# brushed_UAS_Design_2_routed.net
KiCad netlist of a schematic drawn in EAGLE
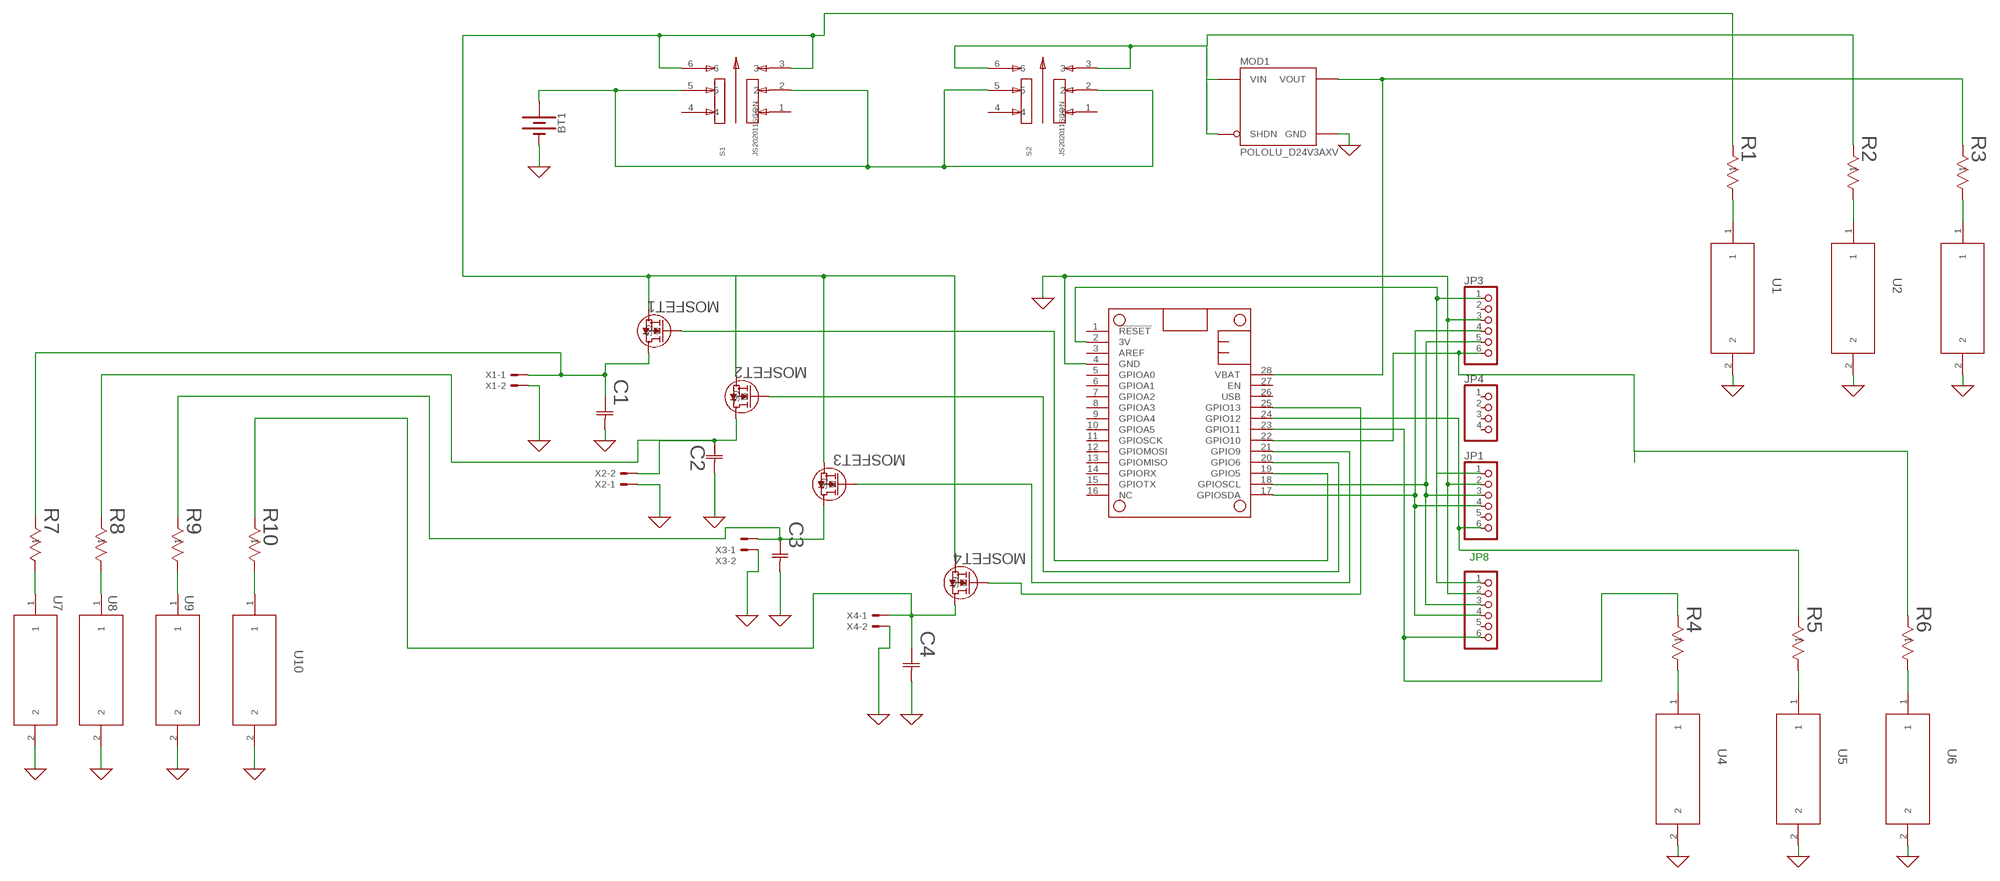
[diagram p0: schematic, sheet 1, part 1 of 2]
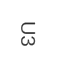
[diagram p1: schematic, sheet 1, part 2 of 2]

(export (version "E")
  (design (tool "Eeschema 10.0.6"))
  (components
    (comp (ref "BT1")
      (value "BATTERY-18650")
      (footprint "eagle-import:BATTERY_18650-HOLDER")
      (libsource (lib "eagle-import") (part "BATTERY-18650"))
    )
    (comp (ref "C1")
      (value "ECH-U1H102JX5CAP_J1_PAN-M")
      (footprint "eagle-import:CAP_J1_PAN-M")
      (fields (field (name "MANUFACTURER_PART_NUMBER") "ECH-U1H102JX5"))
      (libsource (lib "eagle-import") (part "ECH-U1H102JX5CAP_J1_PAN-M"))
    )
    (comp (ref "C2")
      (value "ECH-U1H102JX5CAP_J1_PAN-M")
      (footprint "eagle-import:CAP_J1_PAN-M")
      (fields (field (name "MANUFACTURER_PART_NUMBER") "ECH-U1H102JX5"))
      (libsource (lib "eagle-import") (part "ECH-U1H102JX5CAP_J1_PAN-M"))
    )
    (comp (ref "C3")
      (value "ECH-U1H102JX5CAP_J1_PAN-M")
      (footprint "eagle-import:CAP_J1_PAN-M")
      (fields (field (name "MANUFACTURER_PART_NUMBER") "ECH-U1H102JX5"))
      (libsource (lib "eagle-import") (part "ECH-U1H102JX5CAP_J1_PAN-M"))
    )
    (comp (ref "C4")
      (value "ECH-U1H102JX5CAP_J1_PAN-M")
      (footprint "eagle-import:CAP_J1_PAN-M")
      (fields (field (name "MANUFACTURER_PART_NUMBER") "ECH-U1H102JX5"))
      (libsource (lib "eagle-import") (part "ECH-U1H102JX5CAP_J1_PAN-M"))
    )
    (comp (ref "JP1")
      (value "HEADER-1X670MIL")
      (footprint "eagle-import:1X06_ROUND_70")
      (libsource (lib "eagle-import") (part "HEADER-1X670MIL"))
    )
    (comp (ref "JP3")
      (value "HEADER-1X676MIL")
      (footprint "eagle-import:1X06_ROUND_76")
      (libsource (lib "eagle-import") (part "HEADER-1X676MIL"))
    )
    (comp (ref "JP4")
      (value "HEADER-1X476MIL")
      (footprint "eagle-import:1X04_ROUND_76")
      (libsource (lib "eagle-import") (part "HEADER-1X476MIL"))
    )
    (comp (ref "JP8")
      (value "HEADER-1X670MIL")
      (footprint "eagle-import:1X06_ROUND_70")
      (libsource (lib "eagle-import") (part "HEADER-1X670MIL"))
    )
    (comp (ref "MOD1")
      (value "POLOLU_D24V3AXV")
      (footprint "eagle-import:POLOLU_D24VXAYV_HC")
      (libsource (lib "eagle-import") (part "POLOLU_D24V3AVX"))
    )
    (comp (ref "MOSFET1")
      (value "SI2342DS-T1-GE3SOT-23_TO-236_VIS-M")
      (footprint "eagle-import:SOT-23_TO-236_VIS-M")
      (fields
        (field (name "MANUFACTURER_PART_NUMBER") "SI2342DS-T1-GE3")
        (field (name "COPYRIGHT") "Copyright (C) 2018 Accelerated Designs. All rights reserved")
      )
      (libsource (lib "eagle-import") (part "SI2342DS-T1-GE3SOT-23_TO-236_VIS-M"))
    )
    (comp (ref "MOSFET2")
      (value "SI2342DS-T1-GE3SOT-23_TO-236_VIS-M")
      (footprint "eagle-import:SOT-23_TO-236_VIS-M")
      (fields
        (field (name "MANUFACTURER_PART_NUMBER") "SI2342DS-T1-GE3")
        (field (name "COPYRIGHT") "Copyright (C) 2018 Accelerated Designs. All rights reserved")
      )
      (libsource (lib "eagle-import") (part "SI2342DS-T1-GE3SOT-23_TO-236_VIS-M"))
    )
    (comp (ref "MOSFET3")
      (value "SI2342DS-T1-GE3SOT-23_TO-236_VIS-M")
      (footprint "eagle-import:SOT-23_TO-236_VIS-M")
      (fields
        (field (name "MANUFACTURER_PART_NUMBER") "SI2342DS-T1-GE3")
        (field (name "COPYRIGHT") "Copyright (C) 2018 Accelerated Designs. All rights reserved")
      )
      (libsource (lib "eagle-import") (part "SI2342DS-T1-GE3SOT-23_TO-236_VIS-M"))
    )
    (comp (ref "MOSFET4")
      (value "SI2342DS-T1-GE3SOT-23_TO-236_VIS-M")
      (footprint "eagle-import:SOT-23_TO-236_VIS-M")
      (fields
        (field (name "MANUFACTURER_PART_NUMBER") "SI2342DS-T1-GE3")
        (field (name "COPYRIGHT") "Copyright (C) 2018 Accelerated Designs. All rights reserved")
      )
      (libsource (lib "eagle-import") (part "SI2342DS-T1-GE3SOT-23_TO-236_VIS-M"))
    )
    (comp (ref "MS1")
      (value "FEATHERWING_NODIM")
      (footprint "eagle-import:FEATHERWING_DIM")
      (libsource (lib "eagle-import") (part "FEATHERWING_NODIM"))
    )
    (comp (ref "R1")
      (value "CR0805-FX-1000ELFBO_CR0805-M")
      (footprint "eagle-import:BO_CR0805-M")
      (fields (field (name "MANUFACTURER_PART_NUMBER") "CR0805-FX-1000ELF"))
      (libsource (lib "eagle-import") (part "CR0805-FX-1000ELFBO_CR0805-M"))
    )
    (comp (ref "R2")
      (value "CR0805-FX-1000ELFBO_CR0805-M")
      (footprint "eagle-import:BO_CR0805-M")
      (fields (field (name "MANUFACTURER_PART_NUMBER") "CR0805-FX-1000ELF"))
      (libsource (lib "eagle-import") (part "CR0805-FX-1000ELFBO_CR0805-M"))
    )
    (comp (ref "R3")
      (value "CR0805-FX-1000ELFBO_CR0805-M")
      (footprint "eagle-import:BO_CR0805-M")
      (fields (field (name "MANUFACTURER_PART_NUMBER") "CR0805-FX-1000ELF"))
      (libsource (lib "eagle-import") (part "CR0805-FX-1000ELFBO_CR0805-M"))
    )
    (comp (ref "R4")
      (value "CR0805-FX-1000ELFBO_CR0805-M")
      (footprint "eagle-import:BO_CR0805-M")
      (fields (field (name "MANUFACTURER_PART_NUMBER") "CR0805-FX-1000ELF"))
      (libsource (lib "eagle-import") (part "CR0805-FX-1000ELFBO_CR0805-M"))
    )
    (comp (ref "R5")
      (value "CR0805-FX-1000ELFBO_CR0805-M")
      (footprint "eagle-import:BO_CR0805-M")
      (fields (field (name "MANUFACTURER_PART_NUMBER") "CR0805-FX-1000ELF"))
      (libsource (lib "eagle-import") (part "CR0805-FX-1000ELFBO_CR0805-M"))
    )
    (comp (ref "R6")
      (value "CR0805-FX-1000ELFBO_CR0805-M")
      (footprint "eagle-import:BO_CR0805-M")
      (fields (field (name "MANUFACTURER_PART_NUMBER") "CR0805-FX-1000ELF"))
      (libsource (lib "eagle-import") (part "CR0805-FX-1000ELFBO_CR0805-M"))
    )
    (comp (ref "R7")
      (value "CR0805-FX-1000ELFBO_CR0805-M")
      (footprint "eagle-import:BO_CR0805-M")
      (fields (field (name "MANUFACTURER_PART_NUMBER") "CR0805-FX-1000ELF"))
      (libsource (lib "eagle-import") (part "CR0805-FX-1000ELFBO_CR0805-M"))
    )
    (comp (ref "R8")
      (value "CR0805-FX-1000ELFBO_CR0805-M")
      (footprint "eagle-import:BO_CR0805-M")
      (fields (field (name "MANUFACTURER_PART_NUMBER") "CR0805-FX-1000ELF"))
      (libsource (lib "eagle-import") (part "CR0805-FX-1000ELFBO_CR0805-M"))
    )
    (comp (ref "R9")
      (value "CR0805-FX-1000ELFBO_CR0805-M")
      (footprint "eagle-import:BO_CR0805-M")
      (fields (field (name "MANUFACTURER_PART_NUMBER") "CR0805-FX-1000ELF"))
      (libsource (lib "eagle-import") (part "CR0805-FX-1000ELFBO_CR0805-M"))
    )
    (comp (ref "R10")
      (value "CR0805-FX-1000ELFBO_CR0805-M")
      (footprint "eagle-import:BO_CR0805-M")
      (fields (field (name "MANUFACTURER_PART_NUMBER") "CR0805-FX-1000ELF"))
      (libsource (lib "eagle-import") (part "CR0805-FX-1000ELFBO_CR0805-M"))
    )
    (comp (ref "S1")
      (value "JS202011SCQN")
      (footprint "eagle-import:SW_JS202011SCQN")
      (fields (field (name "DIGI-KEY_PART_NUMBER") "401-2002-1-ND") (field (name "MF") "C&K"))
      (libsource (lib "eagle-import") (part "JS202011SCQN"))
    )
    (comp (ref "S2")
      (value "JS202011SCQN")
      (footprint "eagle-import:SW_JS202011SCQN")
      (fields (field (name "DIGI-KEY_PART_NUMBER") "401-2002-1-ND") (field (name "MF") "C&K"))
      (libsource (lib "eagle-import") (part "JS202011SCQN"))
    )
    (comp (ref "U1")
      (value "L196L-QBCL196L-QBC_AOP-M")
      (footprint "eagle-import:L196L-QBC_AOP-M")
      (fields
        (field (name "MANUFACTURER_PART_NUMBER") "L196L-QBC")
        (field (name "COPYRIGHT") "Copyright (C) 2018 Accelerated Designs. All rights reserved")
      )
      (libsource (lib "eagle-import") (part "L196L-QBCL196L-QBC_AOP-M"))
    )
    (comp (ref "U2")
      (value "L196L-QBCL196L-QBC_AOP-M")
      (footprint "eagle-import:L196L-QBC_AOP-M")
      (fields
        (field (name "MANUFACTURER_PART_NUMBER") "L196L-QBC")
        (field (name "COPYRIGHT") "Copyright (C) 2018 Accelerated Designs. All rights reserved")
      )
      (libsource (lib "eagle-import") (part "L196L-QBCL196L-QBC_AOP-M"))
    )
    (comp (ref "U3")
      (value "L196L-QBCL196L-QBC_AOP-M")
      (footprint "eagle-import:L196L-QBC_AOP-M")
      (fields
        (field (name "MANUFACTURER_PART_NUMBER") "L196L-QBC")
        (field (name "COPYRIGHT") "Copyright (C) 2018 Accelerated Designs. All rights reserved")
      )
      (libsource (lib "eagle-import") (part "L196L-QBCL196L-QBC_AOP-M"))
    )
    (comp (ref "U4")
      (value "L196L-QBCL196L-QBC_AOP-M")
      (footprint "eagle-import:L196L-QBC_AOP-M")
      (fields
        (field (name "MANUFACTURER_PART_NUMBER") "L196L-QBC")
        (field (name "COPYRIGHT") "Copyright (C) 2018 Accelerated Designs. All rights reserved")
      )
      (libsource (lib "eagle-import") (part "L196L-QBCL196L-QBC_AOP-M"))
    )
    (comp (ref "U5")
      (value "L196L-QBCL196L-QBC_AOP-M")
      (footprint "eagle-import:L196L-QBC_AOP-M")
      (fields
        (field (name "MANUFACTURER_PART_NUMBER") "L196L-QBC")
        (field (name "COPYRIGHT") "Copyright (C) 2018 Accelerated Designs. All rights reserved")
      )
      (libsource (lib "eagle-import") (part "L196L-QBCL196L-QBC_AOP-M"))
    )
    (comp (ref "U6")
      (value "L196L-QBCL196L-QBC_AOP-M")
      (footprint "eagle-import:L196L-QBC_AOP-M")
      (fields
        (field (name "MANUFACTURER_PART_NUMBER") "L196L-QBC")
        (field (name "COPYRIGHT") "Copyright (C) 2018 Accelerated Designs. All rights reserved")
      )
      (libsource (lib "eagle-import") (part "L196L-QBCL196L-QBC_AOP-M"))
    )
    (comp (ref "U7")
      (value "L196L-QBCL196L-QBC_AOP-M")
      (footprint "eagle-import:L196L-QBC_AOP-M")
      (fields
        (field (name "MANUFACTURER_PART_NUMBER") "L196L-QBC")
        (field (name "COPYRIGHT") "Copyright (C) 2018 Accelerated Designs. All rights reserved")
      )
      (libsource (lib "eagle-import") (part "L196L-QBCL196L-QBC_AOP-M"))
    )
    (comp (ref "U8")
      (value "L196L-QBCL196L-QBC_AOP-M")
      (footprint "eagle-import:L196L-QBC_AOP-M")
      (fields
        (field (name "MANUFACTURER_PART_NUMBER") "L196L-QBC")
        (field (name "COPYRIGHT") "Copyright (C) 2018 Accelerated Designs. All rights reserved")
      )
      (libsource (lib "eagle-import") (part "L196L-QBCL196L-QBC_AOP-M"))
    )
    (comp (ref "U9")
      (value "L196L-QBCL196L-QBC_AOP-M")
      (footprint "eagle-import:L196L-QBC_AOP-M")
      (fields
        (field (name "MANUFACTURER_PART_NUMBER") "L196L-QBC")
        (field (name "COPYRIGHT") "Copyright (C) 2018 Accelerated Designs. All rights reserved")
      )
      (libsource (lib "eagle-import") (part "L196L-QBCL196L-QBC_AOP-M"))
    )
    (comp (ref "U10")
      (value "L196L-QBCL196L-QBC_AOP-M")
      (footprint "eagle-import:L196L-QBC_AOP-M")
      (fields
        (field (name "MANUFACTURER_PART_NUMBER") "L196L-QBC")
        (field (name "COPYRIGHT") "Copyright (C) 2018 Accelerated Designs. All rights reserved")
      )
      (libsource (lib "eagle-import") (part "L196L-QBCL196L-QBC_AOP-M"))
    )
    (comp (ref "X1")
      (value "22-23-2021")
      (footprint "eagle-import:22-23-2021")
      (fields (field (name "MF") "MOLEX"))
      (libsource (lib "eagle-import") (part "22-23-2021"))
    )
    (comp (ref "X2")
      (value "22-23-2021")
      (footprint "eagle-import:22-23-2021")
      (fields (field (name "MF") "MOLEX"))
      (libsource (lib "eagle-import") (part "22-23-2021"))
    )
    (comp (ref "X3")
      (value "22-23-2021")
      (footprint "eagle-import:22-23-2021")
      (fields (field (name "MF") "MOLEX"))
      (libsource (lib "eagle-import") (part "22-23-2021"))
    )
    (comp (ref "X4")
      (value "22-23-2021")
      (footprint "eagle-import:22-23-2021")
      (fields (field (name "MF") "MOLEX"))
      (libsource (lib "eagle-import") (part "22-23-2021"))
    )
  )
  (nets
    (net (code "1") (name "/USB") (class "Default")
      (node (ref "MS1") (pin "26") (pinfunction "USB_26") (pintype "power_in"))
    )
    (net (code "2") (name "GND") (class "Default")
      (node (ref "BT1") (pin "GND@1") (pinfunction "-_GND@1") (pintype "power_in"))
      (node (ref "C1") (pin "2") (pinfunction "2_2") (pintype "passive"))
      (node (ref "C2") (pin "2") (pinfunction "2_2") (pintype "passive"))
      (node (ref "C3") (pin "2") (pinfunction "2_2") (pintype "passive"))
      (node (ref "C4") (pin "2") (pinfunction "2_2") (pintype "passive"))
      (node (ref "JP1") (pin "2") (pinfunction "2_2") (pintype "passive"))
      (node (ref "JP3") (pin "3") (pinfunction "3_3") (pintype "passive"))
      (node (ref "JP8") (pin "2") (pinfunction "2_2") (pintype "passive"))
      (node (ref "MOD1") (pin "G") (pinfunction "GND_G") (pintype "power_in"))
      (node (ref "MS1") (pin "4") (pinfunction "GND_4") (pintype "power_in"))
      (node (ref "U1") (pin "2") (pinfunction "2_2") (pintype "passive"))
      (node (ref "U10") (pin "2") (pinfunction "2_2") (pintype "passive"))
      (node (ref "U2") (pin "2") (pinfunction "2_2") (pintype "passive"))
      (node (ref "U3") (pin "2") (pinfunction "2_2") (pintype "passive"))
      (node (ref "U4") (pin "2") (pinfunction "2_2") (pintype "passive"))
      (node (ref "U5") (pin "2") (pinfunction "2_2") (pintype "passive"))
      (node (ref "U6") (pin "2") (pinfunction "2_2") (pintype "passive"))
      (node (ref "U7") (pin "2") (pinfunction "2_2") (pintype "passive"))
      (node (ref "U8") (pin "2") (pinfunction "2_2") (pintype "passive"))
      (node (ref "U9") (pin "2") (pinfunction "2_2") (pintype "passive"))
      (node (ref "X1") (pin "2") (pinfunction "S_2") (pintype "passive"))
      (node (ref "X2") (pin "1") (pinfunction "S_1") (pintype "passive"))
      (node (ref "X3") (pin "2") (pinfunction "S_2") (pintype "passive"))
      (node (ref "X4") (pin "2") (pinfunction "S_2") (pintype "passive"))
    )
    (net (code "3") (name "Net-(BT1-+)") (class "Default")
      (node (ref "BT1") (pin "PWR@1") (pinfunction "+_PWR@1") (pintype "power_in"))
      (node (ref "S1") (pin "2") (pinfunction "2_2") (pintype "passive"))
      (node (ref "S1") (pin "5") (pinfunction "5_5") (pintype "passive"))
      (node (ref "S2") (pin "2") (pinfunction "2_2") (pintype "passive"))
      (node (ref "S2") (pin "5") (pinfunction "5_5") (pintype "passive"))
    )
    (net (code "4") (name "Net-(MOD1-SHDN)") (class "Default")
      (node (ref "MOD1") (pin "I") (pinfunction "VIN_I") (pintype "power_in"))
      (node (ref "MOD1") (pin "S") (pinfunction "SHDN_S") (pintype "input"))
      (node (ref "R2") (pin "1") (pinfunction "1_1") (pintype "passive"))
      (node (ref "S2") (pin "3") (pinfunction "3_3") (pintype "passive"))
      (node (ref "S2") (pin "6") (pinfunction "6_6") (pintype "passive"))
    )
    (net (code "5") (name "Net-(MOD1-VOUT)") (class "Default")
      (node (ref "MOD1") (pin "O") (pinfunction "VOUT_O") (pintype "output"))
      (node (ref "MS1") (pin "28") (pinfunction "VBAT_28") (pintype "power_in"))
      (node (ref "R3") (pin "1") (pinfunction "1_1") (pintype "passive"))
    )
    (net (code "6") (name "Net-(MOSFET1-D)") (class "Default")
      (node (ref "C1") (pin "1") (pinfunction "1_1") (pintype "passive"))
      (node (ref "MOSFET1") (pin "3") (pinfunction "D_3") (pintype "passive"))
      (node (ref "R7") (pin "1") (pinfunction "1_1") (pintype "passive"))
      (node (ref "X1") (pin "1") (pinfunction "S_1") (pintype "passive"))
    )
    (net (code "7") (name "Net-(MOSFET1-G)") (class "Default")
      (node (ref "MOSFET1") (pin "1") (pinfunction "G_1") (pintype "passive"))
      (node (ref "MS1") (pin "19") (pinfunction "GPIO5_19") (pintype "bidirectional"))
    )
    (net (code "8") (name "Net-(MOSFET1-S)") (class "Default")
      (node (ref "MOSFET1") (pin "2") (pinfunction "S_2") (pintype "passive"))
      (node (ref "MOSFET2") (pin "2") (pinfunction "S_2") (pintype "passive"))
      (node (ref "MOSFET3") (pin "2") (pinfunction "S_2") (pintype "passive"))
      (node (ref "MOSFET4") (pin "2") (pinfunction "S_2") (pintype "passive"))
      (node (ref "R1") (pin "1") (pinfunction "1_1") (pintype "passive"))
      (node (ref "S1") (pin "3") (pinfunction "3_3") (pintype "passive"))
      (node (ref "S1") (pin "6") (pinfunction "6_6") (pintype "passive"))
    )
    (net (code "9") (name "Net-(MOSFET2-D)") (class "Default")
      (node (ref "C2") (pin "1") (pinfunction "1_1") (pintype "passive"))
      (node (ref "MOSFET2") (pin "3") (pinfunction "D_3") (pintype "passive"))
      (node (ref "R8") (pin "1") (pinfunction "1_1") (pintype "passive"))
      (node (ref "X2") (pin "2") (pinfunction "S_2") (pintype "passive"))
    )
    (net (code "10") (name "Net-(MOSFET2-G)") (class "Default")
      (node (ref "MOSFET2") (pin "1") (pinfunction "G_1") (pintype "passive"))
      (node (ref "MS1") (pin "20") (pinfunction "GPIO6_20") (pintype "bidirectional"))
    )
    (net (code "11") (name "Net-(MOSFET3-D)") (class "Default")
      (node (ref "C3") (pin "1") (pinfunction "1_1") (pintype "passive"))
      (node (ref "MOSFET3") (pin "3") (pinfunction "D_3") (pintype "passive"))
      (node (ref "R9") (pin "1") (pinfunction "1_1") (pintype "passive"))
      (node (ref "X3") (pin "1") (pinfunction "S_1") (pintype "passive"))
    )
    (net (code "12") (name "Net-(MOSFET3-G)") (class "Default")
      (node (ref "MOSFET3") (pin "1") (pinfunction "G_1") (pintype "passive"))
      (node (ref "MS1") (pin "21") (pinfunction "GPIO9_21") (pintype "bidirectional"))
    )
    (net (code "13") (name "Net-(MOSFET4-D)") (class "Default")
      (node (ref "C4") (pin "1") (pinfunction "1_1") (pintype "passive"))
      (node (ref "MOSFET4") (pin "3") (pinfunction "D_3") (pintype "passive"))
      (node (ref "R10") (pin "1") (pinfunction "1_1") (pintype "passive"))
      (node (ref "X4") (pin "1") (pinfunction "S_1") (pintype "passive"))
    )
    (net (code "14") (name "Net-(MOSFET4-G)") (class "Default")
      (node (ref "MOSFET4") (pin "1") (pinfunction "G_1") (pintype "passive"))
      (node (ref "MS1") (pin "25") (pinfunction "GPIO13_25") (pintype "bidirectional"))
    )
    (net (code "15") (name "Net-(MS1-3V)") (class "Default")
      (node (ref "JP1") (pin "1") (pinfunction "1_1") (pintype "passive"))
      (node (ref "JP3") (pin "1") (pinfunction "1_1") (pintype "passive"))
      (node (ref "JP8") (pin "1") (pinfunction "1_1") (pintype "passive"))
      (node (ref "MS1") (pin "2") (pinfunction "3V_2") (pintype "power_in"))
    )
    (net (code "16") (name "Net-(MS1-GPIO10)") (class "Default")
      (node (ref "JP3") (pin "6") (pinfunction "6_6") (pintype "passive"))
      (node (ref "MS1") (pin "22") (pinfunction "GPIO10_22") (pintype "bidirectional"))
      (node (ref "R6") (pin "1") (pinfunction "1_1") (pintype "passive"))
    )
    (net (code "17") (name "Net-(MS1-GPIO11)") (class "Default")
      (node (ref "JP8") (pin "6") (pinfunction "6_6") (pintype "passive"))
      (node (ref "MS1") (pin "23") (pinfunction "GPIO11_23") (pintype "bidirectional"))
      (node (ref "R4") (pin "1") (pinfunction "1_1") (pintype "passive"))
    )
    (net (code "18") (name "Net-(MS1-GPIO12)") (class "Default")
      (node (ref "JP1") (pin "6") (pinfunction "6_6") (pintype "passive"))
      (node (ref "MS1") (pin "24") (pinfunction "GPIO12_24") (pintype "bidirectional"))
      (node (ref "R5") (pin "1") (pinfunction "1_1") (pintype "passive"))
    )
    (net (code "19") (name "Net-(MS1-GPIOSCL)") (class "Default")
      (node (ref "JP1") (pin "3") (pinfunction "3_3") (pintype "passive"))
      (node (ref "JP3") (pin "5") (pinfunction "5_5") (pintype "passive"))
      (node (ref "JP8") (pin "3") (pinfunction "3_3") (pintype "passive"))
      (node (ref "MS1") (pin "18") (pinfunction "GPIOSCL_18") (pintype "bidirectional"))
    )
    (net (code "20") (name "Net-(MS1-GPIOSDA)") (class "Default")
      (node (ref "JP1") (pin "4") (pinfunction "4_4") (pintype "passive"))
      (node (ref "JP3") (pin "4") (pinfunction "4_4") (pintype "passive"))
      (node (ref "JP8") (pin "4") (pinfunction "4_4") (pintype "passive"))
      (node (ref "MS1") (pin "17") (pinfunction "GPIOSDA_17") (pintype "bidirectional"))
    )
    (net (code "21") (name "Net-(R1-Pad2)") (class "Default")
      (node (ref "R1") (pin "2") (pinfunction "2_2") (pintype "passive"))
      (node (ref "U1") (pin "1") (pinfunction "1_1") (pintype "passive"))
    )
    (net (code "22") (name "Net-(R2-Pad2)") (class "Default")
      (node (ref "R2") (pin "2") (pinfunction "2_2") (pintype "passive"))
      (node (ref "U2") (pin "1") (pinfunction "1_1") (pintype "passive"))
    )
    (net (code "23") (name "Net-(R3-Pad2)") (class "Default")
      (node (ref "R3") (pin "2") (pinfunction "2_2") (pintype "passive"))
      (node (ref "U3") (pin "1") (pinfunction "1_1") (pintype "passive"))
    )
    (net (code "24") (name "Net-(R4-Pad2)") (class "Default")
      (node (ref "R4") (pin "2") (pinfunction "2_2") (pintype "passive"))
      (node (ref "U4") (pin "1") (pinfunction "1_1") (pintype "passive"))
    )
    (net (code "25") (name "Net-(R5-Pad2)") (class "Default")
      (node (ref "R5") (pin "2") (pinfunction "2_2") (pintype "passive"))
      (node (ref "U5") (pin "1") (pinfunction "1_1") (pintype "passive"))
    )
    (net (code "26") (name "Net-(R6-Pad2)") (class "Default")
      (node (ref "R6") (pin "2") (pinfunction "2_2") (pintype "passive"))
      (node (ref "U6") (pin "1") (pinfunction "1_1") (pintype "passive"))
    )
    (net (code "27") (name "Net-(R7-Pad2)") (class "Default")
      (node (ref "R7") (pin "2") (pinfunction "2_2") (pintype "passive"))
      (node (ref "U7") (pin "1") (pinfunction "1_1") (pintype "passive"))
    )
    (net (code "28") (name "Net-(R8-Pad2)") (class "Default")
      (node (ref "R8") (pin "2") (pinfunction "2_2") (pintype "passive"))
      (node (ref "U8") (pin "1") (pinfunction "1_1") (pintype "passive"))
    )
    (net (code "29") (name "Net-(R9-Pad2)") (class "Default")
      (node (ref "R9") (pin "2") (pinfunction "2_2") (pintype "passive"))
      (node (ref "U9") (pin "1") (pinfunction "1_1") (pintype "passive"))
    )
    (net (code "30") (name "Net-(R10-Pad2)") (class "Default")
      (node (ref "R10") (pin "2") (pinfunction "2_2") (pintype "passive"))
      (node (ref "U10") (pin "1") (pinfunction "1_1") (pintype "passive"))
    )
    (net (code "31") (name "unconnected-(JP1-Pad5)") (class "Default")
      (node (ref "JP1") (pin "5") (pinfunction "5_5") (pintype "passive"))
    )
    (net (code "32") (name "unconnected-(JP3-Pad2)") (class "Default")
      (node (ref "JP3") (pin "2") (pinfunction "2_2") (pintype "passive"))
    )
    (net (code "33") (name "unconnected-(JP4-Pad1)") (class "Default")
      (node (ref "JP4") (pin "1") (pinfunction "1_1") (pintype "passive"))
    )
    (net (code "34") (name "unconnected-(JP4-Pad2)") (class "Default")
      (node (ref "JP4") (pin "2") (pinfunction "2_2") (pintype "passive"))
    )
    (net (code "35") (name "unconnected-(JP4-Pad3)") (class "Default")
      (node (ref "JP4") (pin "3") (pinfunction "3_3") (pintype "passive"))
    )
    (net (code "36") (name "unconnected-(JP4-Pad4)") (class "Default")
      (node (ref "JP4") (pin "4") (pinfunction "4_4") (pintype "passive"))
    )
    (net (code "37") (name "unconnected-(JP8-Pad5)") (class "Default")
      (node (ref "JP8") (pin "5") (pinfunction "5_5") (pintype "passive"))
    )
    (net (code "38") (name "unconnected-(MS1-AREF-Pad3)") (class "Default")
      (node (ref "MS1") (pin "3") (pinfunction "AREF_3") (pintype "passive"))
    )
    (net (code "39") (name "unconnected-(MS1-EN-Pad27)") (class "Default")
      (node (ref "MS1") (pin "27") (pinfunction "EN_27") (pintype "passive"))
    )
    (net (code "40") (name "unconnected-(MS1-GPIOA0-Pad5)") (class "Default")
      (node (ref "MS1") (pin "5") (pinfunction "GPIOA0_5") (pintype "bidirectional"))
    )
    (net (code "41") (name "unconnected-(MS1-GPIOA1-Pad6)") (class "Default")
      (node (ref "MS1") (pin "6") (pinfunction "GPIOA1_6") (pintype "bidirectional"))
    )
    (net (code "42") (name "unconnected-(MS1-GPIOA2-Pad7)") (class "Default")
      (node (ref "MS1") (pin "7") (pinfunction "GPIOA2_7") (pintype "bidirectional"))
    )
    (net (code "43") (name "unconnected-(MS1-GPIOA3-Pad8)") (class "Default")
      (node (ref "MS1") (pin "8") (pinfunction "GPIOA3_8") (pintype "bidirectional"))
    )
    (net (code "44") (name "unconnected-(MS1-GPIOA4-Pad9)") (class "Default")
      (node (ref "MS1") (pin "9") (pinfunction "GPIOA4_9") (pintype "bidirectional"))
    )
    (net (code "45") (name "unconnected-(MS1-GPIOA5-Pad10)") (class "Default")
      (node (ref "MS1") (pin "10") (pinfunction "GPIOA5_10") (pintype "bidirectional"))
    )
    (net (code "46") (name "unconnected-(MS1-GPIOMISO-Pad13)") (class "Default")
      (node (ref "MS1") (pin "13") (pinfunction "GPIOMISO_13") (pintype "bidirectional"))
    )
    (net (code "47") (name "unconnected-(MS1-GPIOMOSI-Pad12)") (class "Default")
      (node (ref "MS1") (pin "12") (pinfunction "GPIOMOSI_12") (pintype "bidirectional"))
    )
    (net (code "48") (name "unconnected-(MS1-GPIORX-Pad14)") (class "Default")
      (node (ref "MS1") (pin "14") (pinfunction "GPIORX_14") (pintype "bidirectional"))
    )
    (net (code "49") (name "unconnected-(MS1-GPIOSCK-Pad11)") (class "Default")
      (node (ref "MS1") (pin "11") (pinfunction "GPIOSCK_11") (pintype "bidirectional"))
    )
    (net (code "50") (name "unconnected-(MS1-GPIOTX-Pad15)") (class "Default")
      (node (ref "MS1") (pin "15") (pinfunction "GPIOTX_15") (pintype "bidirectional"))
    )
    (net (code "51") (name "unconnected-(MS1-NC-Pad16)") (class "Default")
      (node (ref "MS1") (pin "16") (pinfunction "NC_16") (pintype "passive"))
    )
    (net (code "52") (name "unconnected-(MS1-~{RESET}-Pad1)") (class "Default")
      (node (ref "MS1") (pin "1") (pinfunction "~{RESET}_1") (pintype "input"))
    )
    (net (code "53") (name "unconnected-(S1-Pad1)") (class "Default")
      (node (ref "S1") (pin "1") (pinfunction "1_1") (pintype "passive"))
    )
    (net (code "54") (name "unconnected-(S1-Pad4)") (class "Default")
      (node (ref "S1") (pin "4") (pinfunction "4_4") (pintype "passive"))
    )
    (net (code "55") (name "unconnected-(S2-Pad1)") (class "Default")
      (node (ref "S2") (pin "1") (pinfunction "1_1") (pintype "passive"))
    )
    (net (code "56") (name "unconnected-(S2-Pad4)") (class "Default")
      (node (ref "S2") (pin "4") (pinfunction "4_4") (pintype "passive"))
    )
  )
)
